# LightLink_V3.net
KiCad netlist of a schematic drawn in Altium Designer
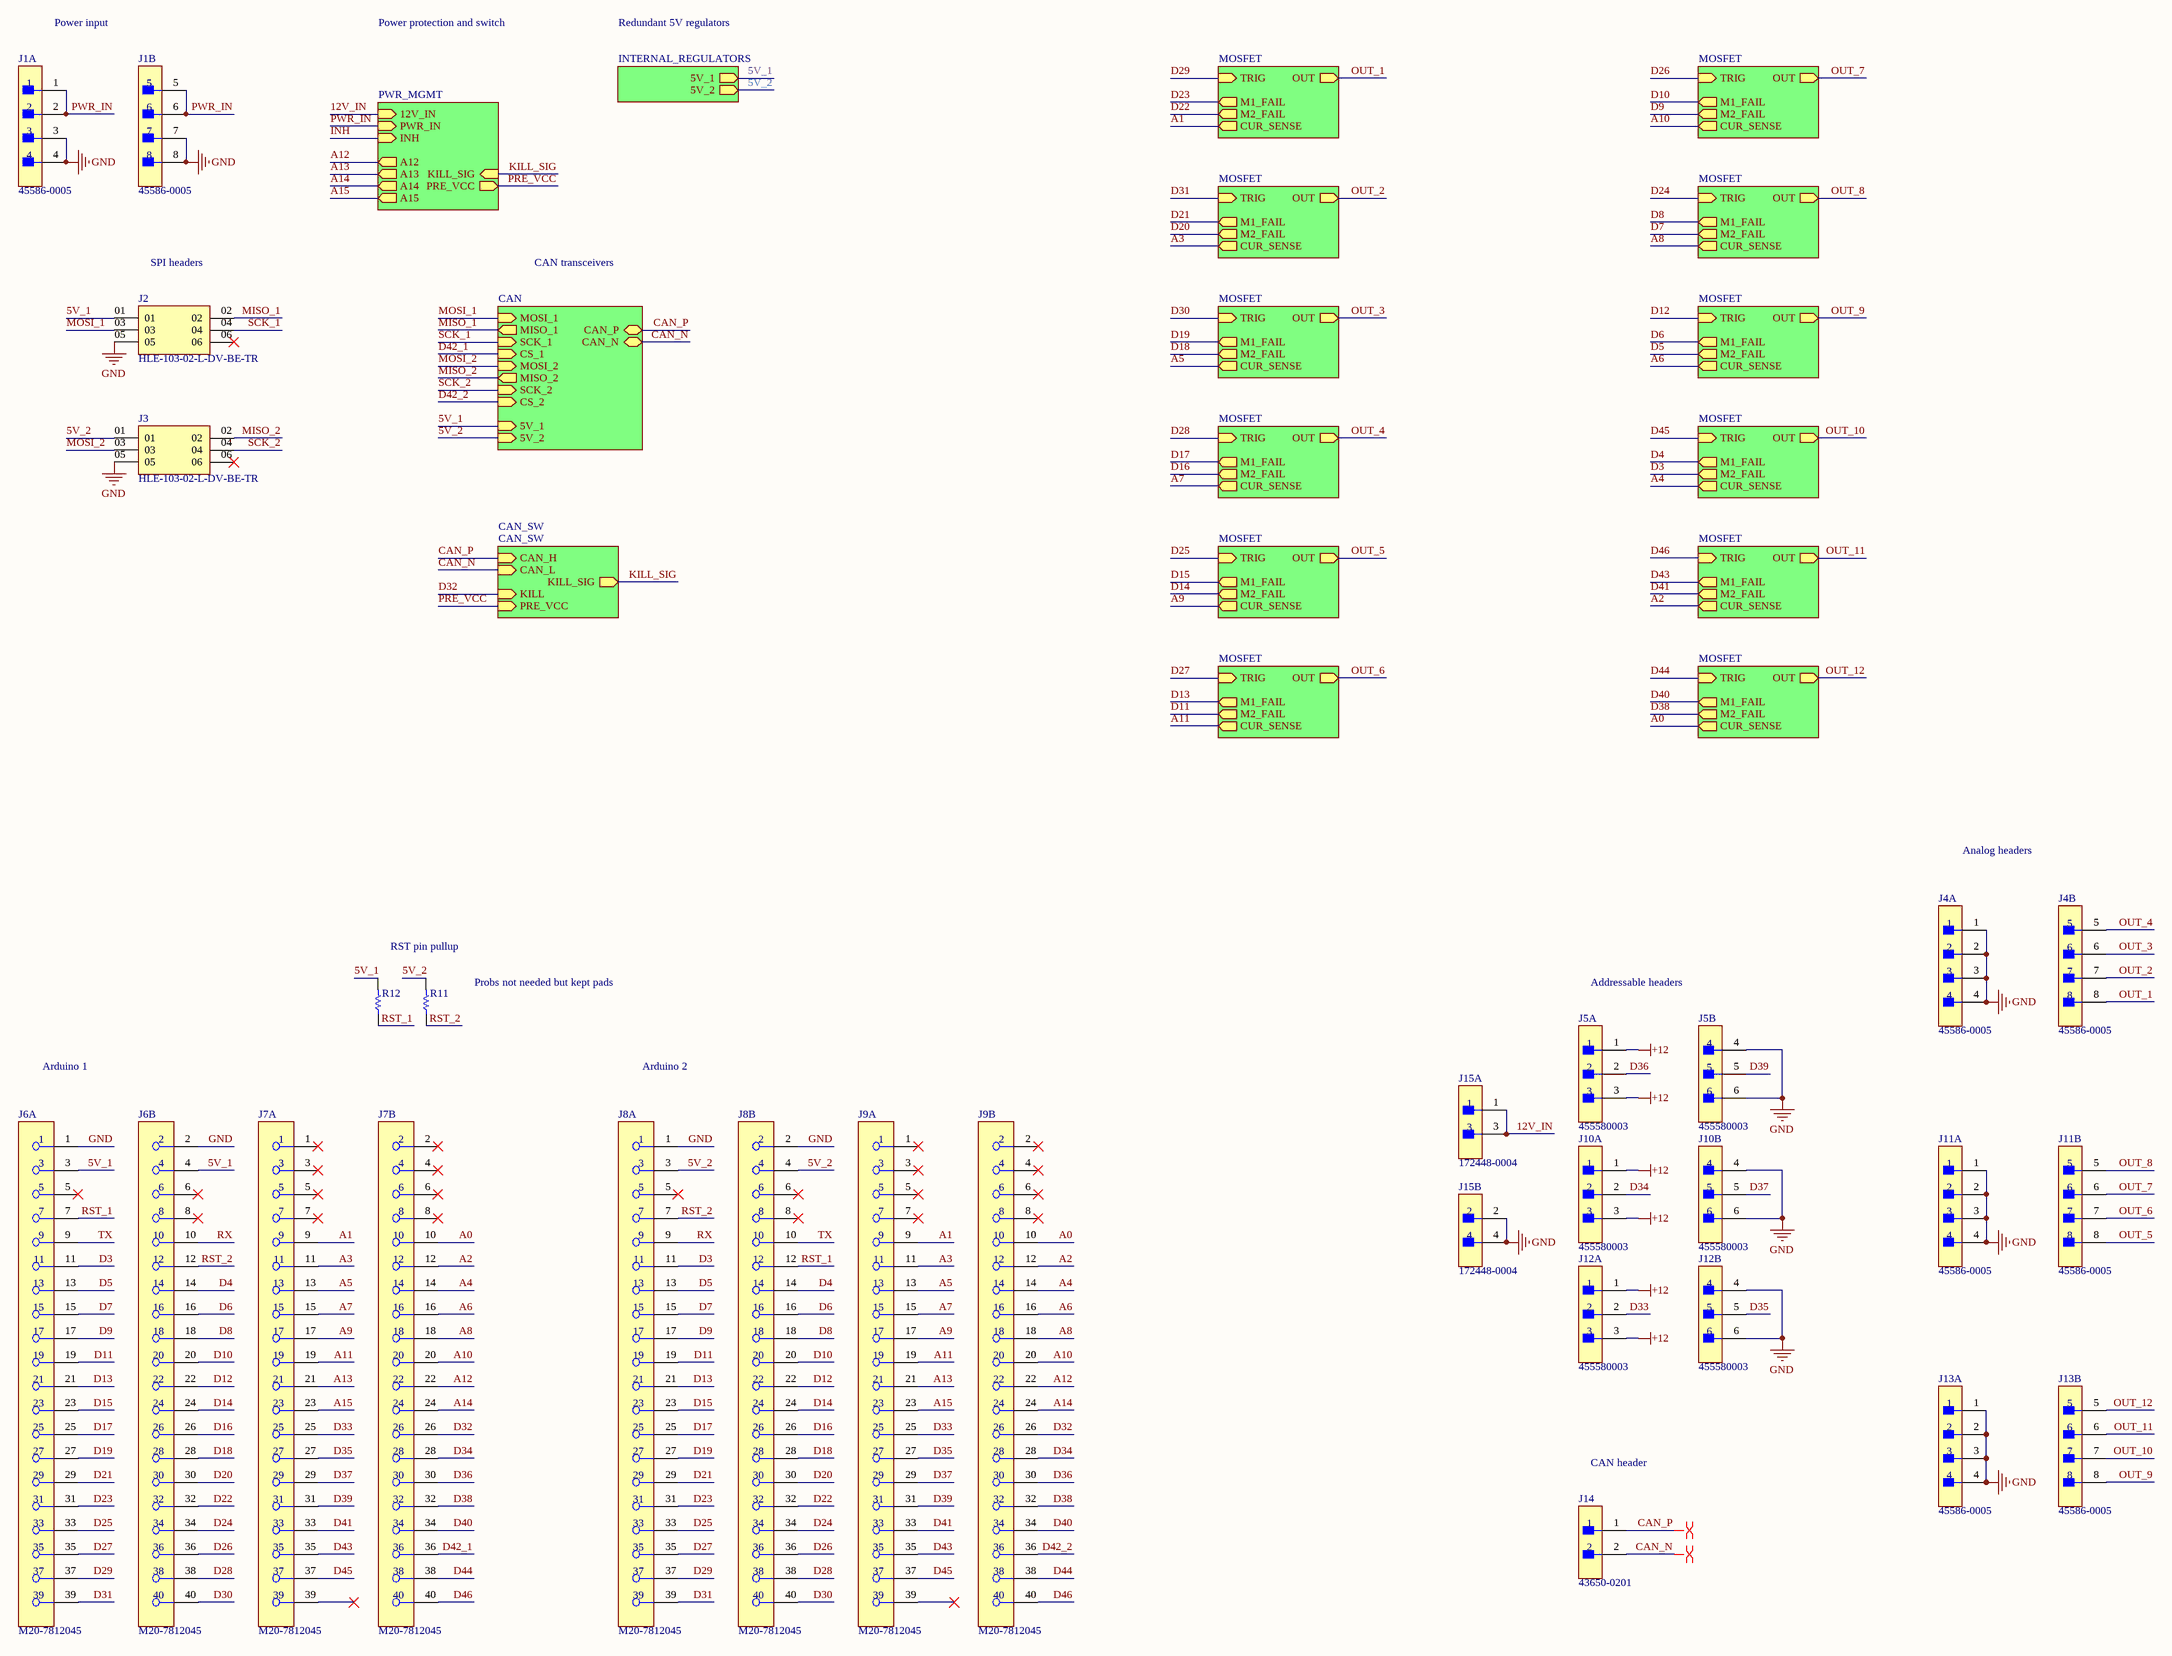
[diagram p0: LightLink_V3.SchDoc]

(export (version "E")
  (design (tool "Eeschema 10.0.6"))
  (components
    (comp (ref "J1")
      (value "45586-0005")
      (footprint "FP-45586-0005-MFG")
      (description "CONN HEADER R/A 8POS 4.2MM")
      (libsource (lib "Altium Content Vault") (part "85438c39ca9ef07d43bb2e97c52bc44"))
    )
    (comp (ref "J2")
      (value "HLE-103-02-L-DV-BE-TR")
      (footprint "SAMTEC_HLE-103-02-L-DV-BE-TR")
      (fields (field (name "MF") "Samtec"))
      (libsource (lib "uORocketry Hardware") (part "HLE-103-02-L-DV-BE-TR"))
    )
    (comp (ref "J3")
      (value "HLE-103-02-L-DV-BE-TR")
      (footprint "SAMTEC_HLE-103-02-L-DV-BE-TR")
      (fields (field (name "MF") "Samtec"))
      (libsource (lib "uORocketry Hardware") (part "HLE-103-02-L-DV-BE-TR"))
    )
    (comp (ref "J4")
      (value "45586-0005")
      (footprint "FP-45586-0005-MFG")
      (description "CONN HEADER R/A 8POS 4.2MM")
      (libsource (lib "Altium Content Vault") (part "85438c39ca9ef07d43bb2e97c52bc44"))
    )
    (comp (ref "J5")
      (value "455580003")
      (footprint "FP-455580003-MFG")
      (description "CONN HEADER R/A 6POS 4.2MM")
      (fields
        (field (name "OCTOPART") "https://octopart.com/45558-0003-molex-7672845")
        (field (name "MANUFACTURER") "Molex")
      )
      (libsource (lib "Altium Content Vault") (part "bb9cbdb24149a20ba329b4e86909569"))
    )
    (comp (ref "J6")
      (value "M20-7812045")
      (footprint "FP-M20-7812045-MFG")
      (description "CONN RCPT 40POS 0.1 GOLD SMD")
      (libsource (lib "Altium Content Vault") (part "7acf1c4a8db21028d11741a46a6ec78"))
    )
    (comp (ref "J7")
      (value "M20-7812045")
      (footprint "FP-M20-7812045-MFG")
      (description "CONN RCPT 40POS 0.1 GOLD SMD")
      (libsource (lib "Altium Content Vault") (part "7acf1c4a8db21028d11741a46a6ec78"))
    )
    (comp (ref "J8")
      (value "M20-7812045")
      (footprint "FP-M20-7812045-MFG")
      (description "CONN RCPT 40POS 0.1 GOLD SMD")
      (libsource (lib "Altium Content Vault") (part "7acf1c4a8db21028d11741a46a6ec78"))
    )
    (comp (ref "J9")
      (value "M20-7812045")
      (footprint "FP-M20-7812045-MFG")
      (description "CONN RCPT 40POS 0.1 GOLD SMD")
      (libsource (lib "Altium Content Vault") (part "7acf1c4a8db21028d11741a46a6ec78"))
    )
    (comp (ref "J10")
      (value "455580003")
      (footprint "FP-455580003-MFG")
      (description "CONN HEADER R/A 6POS 4.2MM")
      (fields
        (field (name "OCTOPART") "https://octopart.com/45558-0003-molex-7672845")
        (field (name "MANUFACTURER") "Molex")
      )
      (libsource (lib "Altium Content Vault") (part "bb9cbdb24149a20ba329b4e86909569"))
    )
    (comp (ref "J11")
      (value "45586-0005")
      (footprint "FP-45586-0005-MFG")
      (description "CONN HEADER R/A 8POS 4.2MM")
      (libsource (lib "Altium Content Vault") (part "85438c39ca9ef07d43bb2e97c52bc44"))
    )
    (comp (ref "J12")
      (value "455580003")
      (footprint "FP-455580003-MFG")
      (description "CONN HEADER R/A 6POS 4.2MM")
      (fields
        (field (name "OCTOPART") "https://octopart.com/45558-0003-molex-7672845")
        (field (name "MANUFACTURER") "Molex")
      )
      (libsource (lib "Altium Content Vault") (part "bb9cbdb24149a20ba329b4e86909569"))
    )
    (comp (ref "J13")
      (value "45586-0005")
      (footprint "FP-45586-0005-MFG")
      (description "CONN HEADER R/A 8POS 4.2MM")
      (libsource (lib "Altium Content Vault") (part "85438c39ca9ef07d43bb2e97c52bc44"))
    )
    (comp (ref "J14")
      (value "43650-0201")
      (footprint "FP-43650-0201-MFG")
      (description "CONN HEADER R/A 2POS 3MM")
      (libsource (lib "Altium Content Vault") (part "3bc925449376181038e59eaffc5286c"))
    )
    (comp (ref "J15")
      (value "172448-0004")
      (footprint "FP-39-30-1041-MFG")
      (description "Different component but holes should line up. Original P/N is 39-30-1041")
      (fields
        (field (name "MANUFACTURER") "Molex")
        (field (name "OCTOPART") "https://octopart.com/39-30-1041-molex-276737")
      )
      (libsource (lib "Altium Content Vault") (part "1621473add15499e993d6bbd36d0f06"))
    )
    (comp (ref "R11")
      (value "ERJ3EKF1002V")
      (footprint "RESC1609X55X30LL15T15")
      (description "Chip Resistor, 10 KOhm, +/- 1%, 0.1 W, -55 to 155 degC, 0603 (1608 Metric), RoHS, Tape and Reel")
      (fields (field (name "TOLERANCE") "1%") (field (name "MANUFACTURER") "Panasonic"))
      (libsource (lib "Altium Content Vault") (part "RES-2"))
    )
    (comp (ref "R12")
      (value "ERJ3EKF1002V")
      (footprint "RESC1609X55X30LL15T15")
      (description "Chip Resistor, 10 KOhm, +/- 1%, 0.1 W, -55 to 155 degC, 0603 (1608 Metric), RoHS, Tape and Reel")
      (fields (field (name "TOLERANCE") "1%") (field (name "MANUFACTURER") "Panasonic"))
      (libsource (lib "Altium Content Vault") (part "RES-2"))
    )
  )
  (nets
    (net (code "1") (name "+12") (class "Default")
      (node (ref "J10") (pin "1") (pinfunction "1_1") (pintype "passive"))
      (node (ref "J10") (pin "3") (pinfunction "3_3") (pintype "passive"))
      (node (ref "J12") (pin "1") (pinfunction "1_1") (pintype "passive"))
      (node (ref "J12") (pin "3") (pinfunction "3_3") (pintype "passive"))
      (node (ref "J5") (pin "1") (pinfunction "1_1") (pintype "passive"))
      (node (ref "J5") (pin "3") (pinfunction "3_3") (pintype "passive"))
    )
    (net (code "2") (name "/5V_1") (class "Default")
      (node (ref "J2") (pin "01") (pinfunction "01_01") (pintype "passive"))
      (node (ref "J6") (pin "3") (pinfunction "3_3") (pintype "passive"))
      (node (ref "J6") (pin "4") (pinfunction "4_4") (pintype "passive"))
      (node (ref "R12") (pin "2") (pinfunction "2_2") (pintype "passive"))
    )
    (net (code "3") (name "/5V_2") (class "Default")
      (node (ref "J3") (pin "01") (pinfunction "01_01") (pintype "passive"))
      (node (ref "J8") (pin "3") (pinfunction "3_3") (pintype "passive"))
      (node (ref "J8") (pin "4") (pinfunction "4_4") (pintype "passive"))
      (node (ref "R11") (pin "2") (pinfunction "2_2") (pintype "passive"))
    )
    (net (code "4") (name "/12V_IN") (class "Default")
      (node (ref "J15") (pin "1") (pinfunction "1_1") (pintype "passive"))
      (node (ref "J15") (pin "3") (pinfunction "3_3") (pintype "passive"))
    )
    (net (code "5") (name "/A0") (class "Default")
      (node (ref "J7") (pin "10") (pinfunction "10_10") (pintype "passive"))
      (node (ref "J9") (pin "10") (pinfunction "10_10") (pintype "passive"))
    )
    (net (code "6") (name "/A1") (class "Default")
      (node (ref "J7") (pin "9") (pinfunction "9_9") (pintype "passive"))
      (node (ref "J9") (pin "9") (pinfunction "9_9") (pintype "passive"))
    )
    (net (code "7") (name "/A2") (class "Default")
      (node (ref "J7") (pin "12") (pinfunction "12_12") (pintype "passive"))
      (node (ref "J9") (pin "12") (pinfunction "12_12") (pintype "passive"))
    )
    (net (code "8") (name "/A3") (class "Default")
      (node (ref "J7") (pin "11") (pinfunction "11_11") (pintype "passive"))
      (node (ref "J9") (pin "11") (pinfunction "11_11") (pintype "passive"))
    )
    (net (code "9") (name "/A4") (class "Default")
      (node (ref "J7") (pin "14") (pinfunction "14_14") (pintype "passive"))
      (node (ref "J9") (pin "14") (pinfunction "14_14") (pintype "passive"))
    )
    (net (code "10") (name "/A5") (class "Default")
      (node (ref "J7") (pin "13") (pinfunction "13_13") (pintype "passive"))
      (node (ref "J9") (pin "13") (pinfunction "13_13") (pintype "passive"))
    )
    (net (code "11") (name "/A6") (class "Default")
      (node (ref "J7") (pin "16") (pinfunction "16_16") (pintype "passive"))
      (node (ref "J9") (pin "16") (pinfunction "16_16") (pintype "passive"))
    )
    (net (code "12") (name "/A7") (class "Default")
      (node (ref "J7") (pin "15") (pinfunction "15_15") (pintype "passive"))
      (node (ref "J9") (pin "15") (pinfunction "15_15") (pintype "passive"))
    )
    (net (code "13") (name "/A8") (class "Default")
      (node (ref "J7") (pin "18") (pinfunction "18_18") (pintype "passive"))
      (node (ref "J9") (pin "18") (pinfunction "18_18") (pintype "passive"))
    )
    (net (code "14") (name "/A9") (class "Default")
      (node (ref "J7") (pin "17") (pinfunction "17_17") (pintype "passive"))
      (node (ref "J9") (pin "17") (pinfunction "17_17") (pintype "passive"))
    )
    (net (code "15") (name "/A10") (class "Default")
      (node (ref "J7") (pin "20") (pinfunction "20_20") (pintype "passive"))
      (node (ref "J9") (pin "20") (pinfunction "20_20") (pintype "passive"))
    )
    (net (code "16") (name "/A11") (class "Default")
      (node (ref "J7") (pin "19") (pinfunction "19_19") (pintype "passive"))
      (node (ref "J9") (pin "19") (pinfunction "19_19") (pintype "passive"))
    )
    (net (code "17") (name "/A12") (class "Default")
      (node (ref "J7") (pin "22") (pinfunction "22_22") (pintype "passive"))
      (node (ref "J9") (pin "22") (pinfunction "22_22") (pintype "passive"))
    )
    (net (code "18") (name "/A13") (class "Default")
      (node (ref "J7") (pin "21") (pinfunction "21_21") (pintype "passive"))
      (node (ref "J9") (pin "21") (pinfunction "21_21") (pintype "passive"))
    )
    (net (code "19") (name "/A14") (class "Default")
      (node (ref "J7") (pin "24") (pinfunction "24_24") (pintype "passive"))
      (node (ref "J9") (pin "24") (pinfunction "24_24") (pintype "passive"))
    )
    (net (code "20") (name "/A15") (class "Default")
      (node (ref "J7") (pin "23") (pinfunction "23_23") (pintype "passive"))
      (node (ref "J9") (pin "23") (pinfunction "23_23") (pintype "passive"))
    )
    (net (code "21") (name "/CAN_N") (class "Default")
      (node (ref "J14") (pin "2") (pinfunction "2_2") (pintype "passive"))
    )
    (net (code "22") (name "/CAN_P") (class "Default")
      (node (ref "J14") (pin "1") (pinfunction "1_1") (pintype "passive"))
    )
    (net (code "23") (name "/D3") (class "Default")
      (node (ref "J6") (pin "11") (pinfunction "11_11") (pintype "passive"))
      (node (ref "J8") (pin "11") (pinfunction "11_11") (pintype "passive"))
    )
    (net (code "24") (name "/D4") (class "Default")
      (node (ref "J6") (pin "14") (pinfunction "14_14") (pintype "passive"))
      (node (ref "J8") (pin "14") (pinfunction "14_14") (pintype "passive"))
    )
    (net (code "25") (name "/D5") (class "Default")
      (node (ref "J6") (pin "13") (pinfunction "13_13") (pintype "passive"))
      (node (ref "J8") (pin "13") (pinfunction "13_13") (pintype "passive"))
    )
    (net (code "26") (name "/D6") (class "Default")
      (node (ref "J6") (pin "16") (pinfunction "16_16") (pintype "passive"))
      (node (ref "J8") (pin "16") (pinfunction "16_16") (pintype "passive"))
    )
    (net (code "27") (name "/D7") (class "Default")
      (node (ref "J6") (pin "15") (pinfunction "15_15") (pintype "passive"))
      (node (ref "J8") (pin "15") (pinfunction "15_15") (pintype "passive"))
    )
    (net (code "28") (name "/D8") (class "Default")
      (node (ref "J6") (pin "18") (pinfunction "18_18") (pintype "passive"))
      (node (ref "J8") (pin "18") (pinfunction "18_18") (pintype "passive"))
    )
    (net (code "29") (name "/D9") (class "Default")
      (node (ref "J6") (pin "17") (pinfunction "17_17") (pintype "passive"))
      (node (ref "J8") (pin "17") (pinfunction "17_17") (pintype "passive"))
    )
    (net (code "30") (name "/D10") (class "Default")
      (node (ref "J6") (pin "20") (pinfunction "20_20") (pintype "passive"))
      (node (ref "J8") (pin "20") (pinfunction "20_20") (pintype "passive"))
    )
    (net (code "31") (name "/D11") (class "Default")
      (node (ref "J6") (pin "19") (pinfunction "19_19") (pintype "passive"))
      (node (ref "J8") (pin "19") (pinfunction "19_19") (pintype "passive"))
    )
    (net (code "32") (name "/D12") (class "Default")
      (node (ref "J6") (pin "22") (pinfunction "22_22") (pintype "passive"))
      (node (ref "J8") (pin "22") (pinfunction "22_22") (pintype "passive"))
    )
    (net (code "33") (name "/D13") (class "Default")
      (node (ref "J6") (pin "21") (pinfunction "21_21") (pintype "passive"))
      (node (ref "J8") (pin "21") (pinfunction "21_21") (pintype "passive"))
    )
    (net (code "34") (name "/D14") (class "Default")
      (node (ref "J6") (pin "24") (pinfunction "24_24") (pintype "passive"))
      (node (ref "J8") (pin "24") (pinfunction "24_24") (pintype "passive"))
    )
    (net (code "35") (name "/D15") (class "Default")
      (node (ref "J6") (pin "23") (pinfunction "23_23") (pintype "passive"))
      (node (ref "J8") (pin "23") (pinfunction "23_23") (pintype "passive"))
    )
    (net (code "36") (name "/D16") (class "Default")
      (node (ref "J6") (pin "26") (pinfunction "26_26") (pintype "passive"))
      (node (ref "J8") (pin "26") (pinfunction "26_26") (pintype "passive"))
    )
    (net (code "37") (name "/D17") (class "Default")
      (node (ref "J6") (pin "25") (pinfunction "25_25") (pintype "passive"))
      (node (ref "J8") (pin "25") (pinfunction "25_25") (pintype "passive"))
    )
    (net (code "38") (name "/D18") (class "Default")
      (node (ref "J6") (pin "28") (pinfunction "28_28") (pintype "passive"))
      (node (ref "J8") (pin "28") (pinfunction "28_28") (pintype "passive"))
    )
    (net (code "39") (name "/D19") (class "Default")
      (node (ref "J6") (pin "27") (pinfunction "27_27") (pintype "passive"))
      (node (ref "J8") (pin "27") (pinfunction "27_27") (pintype "passive"))
    )
    (net (code "40") (name "/D20") (class "Default")
      (node (ref "J6") (pin "30") (pinfunction "30_30") (pintype "passive"))
      (node (ref "J8") (pin "30") (pinfunction "30_30") (pintype "passive"))
    )
    (net (code "41") (name "/D21") (class "Default")
      (node (ref "J6") (pin "29") (pinfunction "29_29") (pintype "passive"))
      (node (ref "J8") (pin "29") (pinfunction "29_29") (pintype "passive"))
    )
    (net (code "42") (name "/D22") (class "Default")
      (node (ref "J6") (pin "32") (pinfunction "32_32") (pintype "passive"))
      (node (ref "J8") (pin "32") (pinfunction "32_32") (pintype "passive"))
    )
    (net (code "43") (name "/D23") (class "Default")
      (node (ref "J6") (pin "31") (pinfunction "31_31") (pintype "passive"))
      (node (ref "J8") (pin "31") (pinfunction "31_31") (pintype "passive"))
    )
    (net (code "44") (name "/D24") (class "Default")
      (node (ref "J6") (pin "34") (pinfunction "34_34") (pintype "passive"))
      (node (ref "J8") (pin "34") (pinfunction "34_34") (pintype "passive"))
    )
    (net (code "45") (name "/D25") (class "Default")
      (node (ref "J6") (pin "33") (pinfunction "33_33") (pintype "passive"))
      (node (ref "J8") (pin "33") (pinfunction "33_33") (pintype "passive"))
    )
    (net (code "46") (name "/D26") (class "Default")
      (node (ref "J6") (pin "36") (pinfunction "36_36") (pintype "passive"))
      (node (ref "J8") (pin "36") (pinfunction "36_36") (pintype "passive"))
    )
    (net (code "47") (name "/D27") (class "Default")
      (node (ref "J6") (pin "35") (pinfunction "35_35") (pintype "passive"))
      (node (ref "J8") (pin "35") (pinfunction "35_35") (pintype "passive"))
    )
    (net (code "48") (name "/D28") (class "Default")
      (node (ref "J6") (pin "38") (pinfunction "38_38") (pintype "passive"))
      (node (ref "J8") (pin "38") (pinfunction "38_38") (pintype "passive"))
    )
    (net (code "49") (name "/D29") (class "Default")
      (node (ref "J6") (pin "37") (pinfunction "37_37") (pintype "passive"))
      (node (ref "J8") (pin "37") (pinfunction "37_37") (pintype "passive"))
    )
    (net (code "50") (name "/D30") (class "Default")
      (node (ref "J6") (pin "40") (pinfunction "40_40") (pintype "passive"))
      (node (ref "J8") (pin "40") (pinfunction "40_40") (pintype "passive"))
    )
    (net (code "51") (name "/D31") (class "Default")
      (node (ref "J6") (pin "39") (pinfunction "39_39") (pintype "passive"))
      (node (ref "J8") (pin "39") (pinfunction "39_39") (pintype "passive"))
    )
    (net (code "52") (name "/D32") (class "Default")
      (node (ref "J7") (pin "26") (pinfunction "26_26") (pintype "passive"))
      (node (ref "J9") (pin "26") (pinfunction "26_26") (pintype "passive"))
    )
    (net (code "53") (name "/D33") (class "Default")
      (node (ref "J12") (pin "2") (pinfunction "2_2") (pintype "passive"))
      (node (ref "J7") (pin "25") (pinfunction "25_25") (pintype "passive"))
      (node (ref "J9") (pin "25") (pinfunction "25_25") (pintype "passive"))
    )
    (net (code "54") (name "/D34") (class "Default")
      (node (ref "J10") (pin "2") (pinfunction "2_2") (pintype "passive"))
      (node (ref "J7") (pin "28") (pinfunction "28_28") (pintype "passive"))
      (node (ref "J9") (pin "28") (pinfunction "28_28") (pintype "passive"))
    )
    (net (code "55") (name "/D35") (class "Default")
      (node (ref "J12") (pin "5") (pinfunction "5_5") (pintype "passive"))
      (node (ref "J7") (pin "27") (pinfunction "27_27") (pintype "passive"))
      (node (ref "J9") (pin "27") (pinfunction "27_27") (pintype "passive"))
    )
    (net (code "56") (name "/D36") (class "Default")
      (node (ref "J5") (pin "2") (pinfunction "2_2") (pintype "passive"))
      (node (ref "J7") (pin "30") (pinfunction "30_30") (pintype "passive"))
      (node (ref "J9") (pin "30") (pinfunction "30_30") (pintype "passive"))
    )
    (net (code "57") (name "/D37") (class "Default")
      (node (ref "J10") (pin "5") (pinfunction "5_5") (pintype "passive"))
      (node (ref "J7") (pin "29") (pinfunction "29_29") (pintype "passive"))
      (node (ref "J9") (pin "29") (pinfunction "29_29") (pintype "passive"))
    )
    (net (code "58") (name "/D38") (class "Default")
      (node (ref "J7") (pin "32") (pinfunction "32_32") (pintype "passive"))
      (node (ref "J9") (pin "32") (pinfunction "32_32") (pintype "passive"))
    )
    (net (code "59") (name "/D39") (class "Default")
      (node (ref "J5") (pin "5") (pinfunction "5_5") (pintype "passive"))
      (node (ref "J7") (pin "31") (pinfunction "31_31") (pintype "passive"))
      (node (ref "J9") (pin "31") (pinfunction "31_31") (pintype "passive"))
    )
    (net (code "60") (name "/D40") (class "Default")
      (node (ref "J7") (pin "34") (pinfunction "34_34") (pintype "passive"))
      (node (ref "J9") (pin "34") (pinfunction "34_34") (pintype "passive"))
    )
    (net (code "61") (name "/D41") (class "Default")
      (node (ref "J7") (pin "33") (pinfunction "33_33") (pintype "passive"))
      (node (ref "J9") (pin "33") (pinfunction "33_33") (pintype "passive"))
    )
    (net (code "62") (name "/D42_1") (class "Default")
      (node (ref "J7") (pin "36") (pinfunction "36_36") (pintype "passive"))
    )
    (net (code "63") (name "/D42_2") (class "Default")
      (node (ref "J9") (pin "36") (pinfunction "36_36") (pintype "passive"))
    )
    (net (code "64") (name "/D43") (class "Default")
      (node (ref "J7") (pin "35") (pinfunction "35_35") (pintype "passive"))
      (node (ref "J9") (pin "35") (pinfunction "35_35") (pintype "passive"))
    )
    (net (code "65") (name "/D44") (class "Default")
      (node (ref "J7") (pin "38") (pinfunction "38_38") (pintype "passive"))
      (node (ref "J9") (pin "38") (pinfunction "38_38") (pintype "passive"))
    )
    (net (code "66") (name "/D45") (class "Default")
      (node (ref "J7") (pin "37") (pinfunction "37_37") (pintype "passive"))
      (node (ref "J9") (pin "37") (pinfunction "37_37") (pintype "passive"))
    )
    (net (code "67") (name "/D46") (class "Default")
      (node (ref "J7") (pin "40") (pinfunction "40_40") (pintype "passive"))
      (node (ref "J9") (pin "40") (pinfunction "40_40") (pintype "passive"))
    )
    (net (code "70") (name "/MISO_1") (class "Default")
      (node (ref "J2") (pin "02") (pinfunction "02_02") (pintype "passive"))
    )
    (net (code "71") (name "/MISO_2") (class "Default")
      (node (ref "J3") (pin "02") (pinfunction "02_02") (pintype "passive"))
    )
    (net (code "72") (name "/MOSI_1") (class "Default")
      (node (ref "J2") (pin "03") (pinfunction "03_03") (pintype "passive"))
    )
    (net (code "73") (name "/MOSI_2") (class "Default")
      (node (ref "J3") (pin "03") (pinfunction "03_03") (pintype "passive"))
    )
    (net (code "74") (name "/OUT_1") (class "Default")
      (node (ref "J4") (pin "8") (pinfunction "8_8") (pintype "passive"))
    )
    (net (code "75") (name "/OUT_2") (class "Default")
      (node (ref "J4") (pin "7") (pinfunction "7_7") (pintype "passive"))
    )
    (net (code "76") (name "/OUT_3") (class "Default")
      (node (ref "J4") (pin "6") (pinfunction "6_6") (pintype "passive"))
    )
    (net (code "77") (name "/OUT_4") (class "Default")
      (node (ref "J4") (pin "5") (pinfunction "5_5") (pintype "passive"))
    )
    (net (code "78") (name "/OUT_5") (class "Default")
      (node (ref "J11") (pin "8") (pinfunction "8_8") (pintype "passive"))
    )
    (net (code "79") (name "/OUT_6") (class "Default")
      (node (ref "J11") (pin "7") (pinfunction "7_7") (pintype "passive"))
    )
    (net (code "80") (name "/OUT_7") (class "Default")
      (node (ref "J11") (pin "6") (pinfunction "6_6") (pintype "passive"))
    )
    (net (code "81") (name "/OUT_8") (class "Default")
      (node (ref "J11") (pin "5") (pinfunction "5_5") (pintype "passive"))
    )
    (net (code "82") (name "/OUT_9") (class "Default")
      (node (ref "J13") (pin "8") (pinfunction "8_8") (pintype "passive"))
    )
    (net (code "83") (name "/OUT_10") (class "Default")
      (node (ref "J13") (pin "7") (pinfunction "7_7") (pintype "passive"))
    )
    (net (code "84") (name "/OUT_11") (class "Default")
      (node (ref "J13") (pin "6") (pinfunction "6_6") (pintype "passive"))
    )
    (net (code "85") (name "/OUT_12") (class "Default")
      (node (ref "J13") (pin "5") (pinfunction "5_5") (pintype "passive"))
    )
    (net (code "87") (name "/PWR_IN") (class "Default")
      (node (ref "J1") (pin "1") (pinfunction "1_1") (pintype "passive"))
      (node (ref "J1") (pin "2") (pinfunction "2_2") (pintype "passive"))
      (node (ref "J1") (pin "5") (pinfunction "5_5") (pintype "passive"))
      (node (ref "J1") (pin "6") (pinfunction "6_6") (pintype "passive"))
    )
    (net (code "88") (name "/RST_1") (class "Default")
      (node (ref "J6") (pin "7") (pinfunction "7_7") (pintype "passive"))
      (node (ref "J8") (pin "12") (pinfunction "12_12") (pintype "passive"))
      (node (ref "R12") (pin "1") (pinfunction "1_1") (pintype "passive"))
    )
    (net (code "89") (name "/RST_2") (class "Default")
      (node (ref "J6") (pin "12") (pinfunction "12_12") (pintype "passive"))
      (node (ref "J8") (pin "7") (pinfunction "7_7") (pintype "passive"))
      (node (ref "R11") (pin "1") (pinfunction "1_1") (pintype "passive"))
    )
    (net (code "90") (name "/RX") (class "Default")
      (node (ref "J6") (pin "10") (pinfunction "10_10") (pintype "passive"))
      (node (ref "J8") (pin "9") (pinfunction "9_9") (pintype "passive"))
    )
    (net (code "91") (name "/SCK_1") (class "Default")
      (node (ref "J2") (pin "04") (pinfunction "04_04") (pintype "passive"))
    )
    (net (code "92") (name "/SCK_2") (class "Default")
      (node (ref "J3") (pin "04") (pinfunction "04_04") (pintype "passive"))
    )
    (net (code "93") (name "/TX") (class "Default")
      (node (ref "J6") (pin "9") (pinfunction "9_9") (pintype "passive"))
      (node (ref "J8") (pin "10") (pinfunction "10_10") (pintype "passive"))
    )
    (net (code "94") (name "GND") (class "Default")
      (node (ref "J1") (pin "3") (pinfunction "3_3") (pintype "passive"))
      (node (ref "J1") (pin "4") (pinfunction "4_4") (pintype "passive"))
      (node (ref "J1") (pin "7") (pinfunction "7_7") (pintype "passive"))
      (node (ref "J1") (pin "8") (pinfunction "8_8") (pintype "passive"))
      (node (ref "J10") (pin "4") (pinfunction "4_4") (pintype "passive"))
      (node (ref "J10") (pin "6") (pinfunction "6_6") (pintype "passive"))
      (node (ref "J11") (pin "1") (pinfunction "1_1") (pintype "passive"))
      (node (ref "J11") (pin "2") (pinfunction "2_2") (pintype "passive"))
      (node (ref "J11") (pin "3") (pinfunction "3_3") (pintype "passive"))
      (node (ref "J11") (pin "4") (pinfunction "4_4") (pintype "passive"))
      (node (ref "J12") (pin "4") (pinfunction "4_4") (pintype "passive"))
      (node (ref "J12") (pin "6") (pinfunction "6_6") (pintype "passive"))
      (node (ref "J13") (pin "1") (pinfunction "1_1") (pintype "passive"))
      (node (ref "J13") (pin "2") (pinfunction "2_2") (pintype "passive"))
      (node (ref "J13") (pin "3") (pinfunction "3_3") (pintype "passive"))
      (node (ref "J13") (pin "4") (pinfunction "4_4") (pintype "passive"))
      (node (ref "J15") (pin "2") (pinfunction "2_2") (pintype "passive"))
      (node (ref "J15") (pin "4") (pinfunction "4_4") (pintype "passive"))
      (node (ref "J2") (pin "05") (pinfunction "05_05") (pintype "passive"))
      (node (ref "J3") (pin "05") (pinfunction "05_05") (pintype "passive"))
      (node (ref "J4") (pin "1") (pinfunction "1_1") (pintype "passive"))
      (node (ref "J4") (pin "2") (pinfunction "2_2") (pintype "passive"))
      (node (ref "J4") (pin "3") (pinfunction "3_3") (pintype "passive"))
      (node (ref "J4") (pin "4") (pinfunction "4_4") (pintype "passive"))
      (node (ref "J5") (pin "4") (pinfunction "4_4") (pintype "passive"))
      (node (ref "J5") (pin "6") (pinfunction "6_6") (pintype "passive"))
      (node (ref "J6") (pin "1") (pinfunction "1_1") (pintype "passive"))
      (node (ref "J6") (pin "2") (pinfunction "2_2") (pintype "passive"))
      (node (ref "J8") (pin "1") (pinfunction "1_1") (pintype "passive"))
      (node (ref "J8") (pin "2") (pinfunction "2_2") (pintype "passive"))
    )
    (net (code "95") (name "unconnected-(J2-Pad06)") (class "Default")
      (node (ref "J2") (pin "06") (pinfunction "06_06") (pintype "passive+no_connect"))
    )
    (net (code "96") (name "unconnected-(J3-Pad06)") (class "Default")
      (node (ref "J3") (pin "06") (pinfunction "06_06") (pintype "passive+no_connect"))
    )
    (net (code "97") (name "unconnected-(J6-Pad5)") (class "Default")
      (node (ref "J6") (pin "5") (pinfunction "5_5") (pintype "passive+no_connect"))
    )
    (net (code "98") (name "unconnected-(J6-Pad6)") (class "Default")
      (node (ref "J6") (pin "6") (pinfunction "6_6") (pintype "passive+no_connect"))
    )
    (net (code "99") (name "unconnected-(J6-Pad8)") (class "Default")
      (node (ref "J6") (pin "8") (pinfunction "8_8") (pintype "passive+no_connect"))
    )
    (net (code "100") (name "unconnected-(J7-Pad1)") (class "Default")
      (node (ref "J7") (pin "1") (pinfunction "1_1") (pintype "passive+no_connect"))
    )
    (net (code "101") (name "unconnected-(J7-Pad2)") (class "Default")
      (node (ref "J7") (pin "2") (pinfunction "2_2") (pintype "passive+no_connect"))
    )
    (net (code "102") (name "unconnected-(J7-Pad3)") (class "Default")
      (node (ref "J7") (pin "3") (pinfunction "3_3") (pintype "passive+no_connect"))
    )
    (net (code "103") (name "unconnected-(J7-Pad4)") (class "Default")
      (node (ref "J7") (pin "4") (pinfunction "4_4") (pintype "passive+no_connect"))
    )
    (net (code "104") (name "unconnected-(J7-Pad5)") (class "Default")
      (node (ref "J7") (pin "5") (pinfunction "5_5") (pintype "passive+no_connect"))
    )
    (net (code "105") (name "unconnected-(J7-Pad6)") (class "Default")
      (node (ref "J7") (pin "6") (pinfunction "6_6") (pintype "passive+no_connect"))
    )
    (net (code "106") (name "unconnected-(J7-Pad7)") (class "Default")
      (node (ref "J7") (pin "7") (pinfunction "7_7") (pintype "passive+no_connect"))
    )
    (net (code "107") (name "unconnected-(J7-Pad8)") (class "Default")
      (node (ref "J7") (pin "8") (pinfunction "8_8") (pintype "passive+no_connect"))
    )
    (net (code "108") (name "unconnected-(J7-Pad39)") (class "Default")
      (node (ref "J7") (pin "39") (pinfunction "39_39") (pintype "passive+no_connect"))
    )
    (net (code "109") (name "unconnected-(J8-Pad5)") (class "Default")
      (node (ref "J8") (pin "5") (pinfunction "5_5") (pintype "passive+no_connect"))
    )
    (net (code "110") (name "unconnected-(J8-Pad6)") (class "Default")
      (node (ref "J8") (pin "6") (pinfunction "6_6") (pintype "passive+no_connect"))
    )
    (net (code "111") (name "unconnected-(J8-Pad8)") (class "Default")
      (node (ref "J8") (pin "8") (pinfunction "8_8") (pintype "passive+no_connect"))
    )
    (net (code "112") (name "unconnected-(J9-Pad1)") (class "Default")
      (node (ref "J9") (pin "1") (pinfunction "1_1") (pintype "passive+no_connect"))
    )
    (net (code "113") (name "unconnected-(J9-Pad2)") (class "Default")
      (node (ref "J9") (pin "2") (pinfunction "2_2") (pintype "passive+no_connect"))
    )
    (net (code "114") (name "unconnected-(J9-Pad3)") (class "Default")
      (node (ref "J9") (pin "3") (pinfunction "3_3") (pintype "passive+no_connect"))
    )
    (net (code "115") (name "unconnected-(J9-Pad4)") (class "Default")
      (node (ref "J9") (pin "4") (pinfunction "4_4") (pintype "passive+no_connect"))
    )
    (net (code "116") (name "unconnected-(J9-Pad5)") (class "Default")
      (node (ref "J9") (pin "5") (pinfunction "5_5") (pintype "passive+no_connect"))
    )
    (net (code "117") (name "unconnected-(J9-Pad6)") (class "Default")
      (node (ref "J9") (pin "6") (pinfunction "6_6") (pintype "passive+no_connect"))
    )
    (net (code "118") (name "unconnected-(J9-Pad7)") (class "Default")
      (node (ref "J9") (pin "7") (pinfunction "7_7") (pintype "passive+no_connect"))
    )
    (net (code "119") (name "unconnected-(J9-Pad8)") (class "Default")
      (node (ref "J9") (pin "8") (pinfunction "8_8") (pintype "passive+no_connect"))
    )
    (net (code "120") (name "unconnected-(J9-Pad39)") (class "Default")
      (node (ref "J9") (pin "39") (pinfunction "39_39") (pintype "passive+no_connect"))
    )
  )
)
